# SQUAREPOWERV2.net
KiCad netlist of a schematic drawn in EAGLE
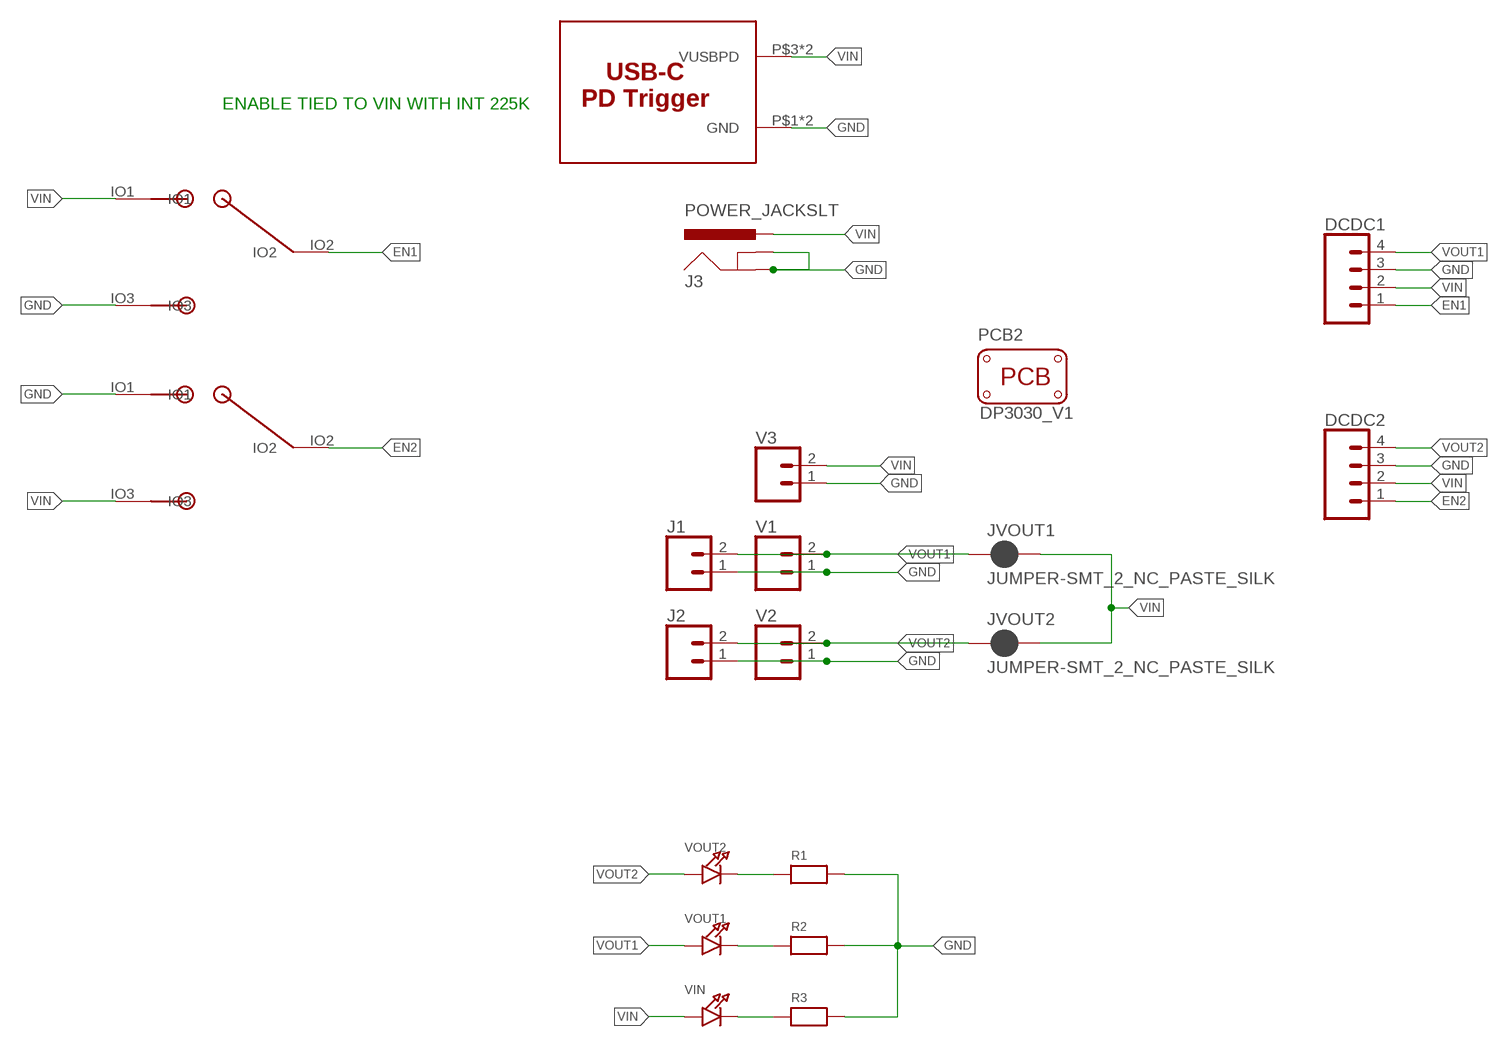
[diagram p0: schematic, sheet 1]

(export (version "E")
  (design (tool "Eeschema 10.0.6"))
  (components
    (comp (ref "DCDC1")
      (value "CONN_04LONGPADS")
      (footprint "eagle-import:1X04_LONGPADS")
      (libsource (lib "eagle-import") (part "CONN_04LONGPADS"))
    )
    (comp (ref "DCDC2")
      (value "CONN_04LONGPADS")
      (footprint "eagle-import:1X04_LONGPADS")
      (libsource (lib "eagle-import") (part "CONN_04LONGPADS"))
    )
    (comp (ref "J1")
      (value "CONN_02")
      (footprint "eagle-import:1X02")
      (libsource (lib "eagle-import") (part "CONN_02"))
    )
    (comp (ref "J2")
      (value "CONN_02")
      (footprint "eagle-import:1X02")
      (libsource (lib "eagle-import") (part "CONN_02"))
    )
    (comp (ref "J3")
      (value "POWER_JACKSLT")
      (footprint "eagle-import:POWER_JACK_SLOT")
      (libsource (lib "eagle-import") (part "POWER_JACKSLT"))
    )
    (comp (ref "JVOUT1")
      (value "JUMPER-SMT_2_NC_PASTE_SILK")
      (footprint "eagle-import:SMT-JUMPER_2_NC_PASTE_SILK")
      (libsource (lib "eagle-import") (part "JUMPER-SMT_2_NC_PASTE_SILK"))
    )
    (comp (ref "JVOUT2")
      (value "JUMPER-SMT_2_NC_PASTE_SILK")
      (footprint "eagle-import:SMT-JUMPER_2_NC_PASTE_SILK")
      (libsource (lib "eagle-import") (part "JUMPER-SMT_2_NC_PASTE_SILK"))
    )
    (comp (ref "PCB2")
      (value "PCB_DP_SQUARE-3X3")
      (footprint "eagle-import:DP3030_V1")
      (fields (field (name "PCB_SIZE") "DP3030_V1"))
      (libsource (lib "eagle-import") (part "PCB_DP_SQUARE-3X3"))
    )
    (comp (ref "R1")
      (value "RESISTOR0805")
      (footprint "eagle-import:0805")
      (libsource (lib "eagle-import") (part "RESISTOR0805"))
    )
    (comp (ref "R2")
      (value "RESISTOR0805")
      (footprint "eagle-import:0805")
      (libsource (lib "eagle-import") (part "RESISTOR0805"))
    )
    (comp (ref "R3")
      (value "RESISTOR0805")
      (footprint "eagle-import:0805")
      (libsource (lib "eagle-import") (part "RESISTOR0805"))
    )
    (comp (ref "U$1")
      (value "SPDT-SWITCH-MSKT-12C00")
      (footprint "eagle-import:MSKT-12C00")
      (libsource (lib "eagle-import") (part "SPDT-SWITCH-MSKT-12C00"))
    )
    (comp (ref "U$2")
      (value "SPDT-SWITCH-MSKT-12C00")
      (footprint "eagle-import:MSKT-12C00")
      (libsource (lib "eagle-import") (part "SPDT-SWITCH-MSKT-12C00"))
    )
    (comp (ref "U$5")
      (value "USB_PD_TRIGGER")
      (footprint "eagle-import:USB-PDTRIGGER")
      (libsource (lib "eagle-import") (part "USB_PD_TRIGGER"))
    )
    (comp (ref "V1")
      (value "CONN_023.5MM")
      (footprint "eagle-import:SCREWTERMINAL-3.5MM-2")
      (libsource (lib "eagle-import") (part "CONN_023.5MM"))
    )
    (comp (ref "V2")
      (value "CONN_023.5MM")
      (footprint "eagle-import:SCREWTERMINAL-3.5MM-2")
      (libsource (lib "eagle-import") (part "CONN_023.5MM"))
    )
    (comp (ref "V3")
      (value "CONN_023.5MM")
      (footprint "eagle-import:SCREWTERMINAL-3.5MM-2")
      (libsource (lib "eagle-import") (part "CONN_023.5MM"))
    )
    (comp (ref "VIN")
      (value "LED0805")
      (footprint "eagle-import:CHIPLED_0805")
      (libsource (lib "eagle-import") (part "LED0805"))
    )
    (comp (ref "VOUT1")
      (value "LED0805")
      (footprint "eagle-import:CHIPLED_0805")
      (libsource (lib "eagle-import") (part "LED0805"))
    )
    (comp (ref "VOUT2")
      (value "LED0805")
      (footprint "eagle-import:CHIPLED_0805")
      (libsource (lib "eagle-import") (part "LED0805"))
    )
  )
  (nets
    (net (code "1") (name "EN1") (class "Default")
      (node (ref "DCDC1") (pin "1") (pinfunction "1_1") (pintype "passive"))
      (node (ref "U$1") (pin "IO2") (pinfunction "IO2_IO2") (pintype "bidirectional"))
    )
    (net (code "2") (name "EN2") (class "Default")
      (node (ref "DCDC2") (pin "1") (pinfunction "1_1") (pintype "passive"))
      (node (ref "U$2") (pin "IO2") (pinfunction "IO2_IO2") (pintype "bidirectional"))
    )
    (net (code "3") (name "GND") (class "Default")
      (node (ref "DCDC1") (pin "3") (pinfunction "3_3") (pintype "passive"))
      (node (ref "DCDC2") (pin "3") (pinfunction "3_3") (pintype "passive"))
      (node (ref "J1") (pin "1") (pinfunction "1_1") (pintype "passive"))
      (node (ref "J2") (pin "1") (pinfunction "1_1") (pintype "passive"))
      (node (ref "J3") (pin "GND@1") (pinfunction "GNDBREAK_GND@1") (pintype "bidirectional"))
      (node (ref "J3") (pin "GND@2") (pinfunction "GND_GND@2") (pintype "bidirectional"))
      (node (ref "R1") (pin "2") (pinfunction "2_2") (pintype "passive"))
      (node (ref "R2") (pin "2") (pinfunction "2_2") (pintype "passive"))
      (node (ref "R3") (pin "2") (pinfunction "2_2") (pintype "passive"))
      (node (ref "U$1") (pin "IO3") (pinfunction "IO3_IO3") (pintype "bidirectional"))
      (node (ref "U$2") (pin "IO1") (pinfunction "IO1_IO1") (pintype "bidirectional"))
      (node (ref "U$5") (pin "P$1") (pinfunction "GND_P$1") (pintype "bidirectional"))
      (node (ref "U$5") (pin "P$2") (pinfunction "GND_P$2") (pintype "bidirectional"))
      (node (ref "V1") (pin "1") (pinfunction "1_1") (pintype "passive"))
      (node (ref "V2") (pin "1") (pinfunction "1_1") (pintype "passive"))
      (node (ref "V3") (pin "1") (pinfunction "1_1") (pintype "passive"))
    )
    (net (code "4") (name "Net-(R1-Pad1)") (class "Default")
      (node (ref "R1") (pin "1") (pinfunction "1_1") (pintype "passive"))
      (node (ref "VOUT2") (pin "C") (pinfunction "C_C") (pintype "passive"))
    )
    (net (code "5") (name "Net-(R2-Pad1)") (class "Default")
      (node (ref "R2") (pin "1") (pinfunction "1_1") (pintype "passive"))
      (node (ref "VOUT1") (pin "C") (pinfunction "C_C") (pintype "passive"))
    )
    (net (code "6") (name "Net-(R3-Pad1)") (class "Default")
      (node (ref "R3") (pin "1") (pinfunction "1_1") (pintype "passive"))
      (node (ref "VIN") (pin "C") (pinfunction "C_C") (pintype "passive"))
    )
    (net (code "7") (name "VIN") (class "Default")
      (node (ref "DCDC1") (pin "2") (pinfunction "2_2") (pintype "passive"))
      (node (ref "DCDC2") (pin "2") (pinfunction "2_2") (pintype "passive"))
      (node (ref "J3") (pin "PWR") (pinfunction "PWR_PWR") (pintype "bidirectional"))
      (node (ref "JVOUT1") (pin "2") (pinfunction "2_2") (pintype "passive"))
      (node (ref "JVOUT2") (pin "2") (pinfunction "2_2") (pintype "passive"))
      (node (ref "U$1") (pin "IO1") (pinfunction "IO1_IO1") (pintype "bidirectional"))
      (node (ref "U$2") (pin "IO3") (pinfunction "IO3_IO3") (pintype "bidirectional"))
      (node (ref "U$5") (pin "P$3") (pinfunction "VUSBPD_P$3") (pintype "bidirectional"))
      (node (ref "U$5") (pin "P$4") (pinfunction "VUSBPD_P$4") (pintype "bidirectional"))
      (node (ref "V3") (pin "2") (pinfunction "2_2") (pintype "passive"))
      (node (ref "VIN") (pin "A") (pinfunction "A_A") (pintype "passive"))
    )
    (net (code "8") (name "VOUT1") (class "Default")
      (node (ref "DCDC1") (pin "4") (pinfunction "4_4") (pintype "passive"))
      (node (ref "J1") (pin "2") (pinfunction "2_2") (pintype "passive"))
      (node (ref "JVOUT1") (pin "1") (pinfunction "1_1") (pintype "passive"))
      (node (ref "V1") (pin "2") (pinfunction "2_2") (pintype "passive"))
      (node (ref "VOUT1") (pin "A") (pinfunction "A_A") (pintype "passive"))
    )
    (net (code "9") (name "VOUT2") (class "Default")
      (node (ref "DCDC2") (pin "4") (pinfunction "4_4") (pintype "passive"))
      (node (ref "J2") (pin "2") (pinfunction "2_2") (pintype "passive"))
      (node (ref "JVOUT2") (pin "1") (pinfunction "1_1") (pintype "passive"))
      (node (ref "V2") (pin "2") (pinfunction "2_2") (pintype "passive"))
      (node (ref "VOUT2") (pin "A") (pinfunction "A_A") (pintype "passive"))
    )
  )
)
